# pathfiner.net
KiCad netlist of a schematic drawn in EAGLE
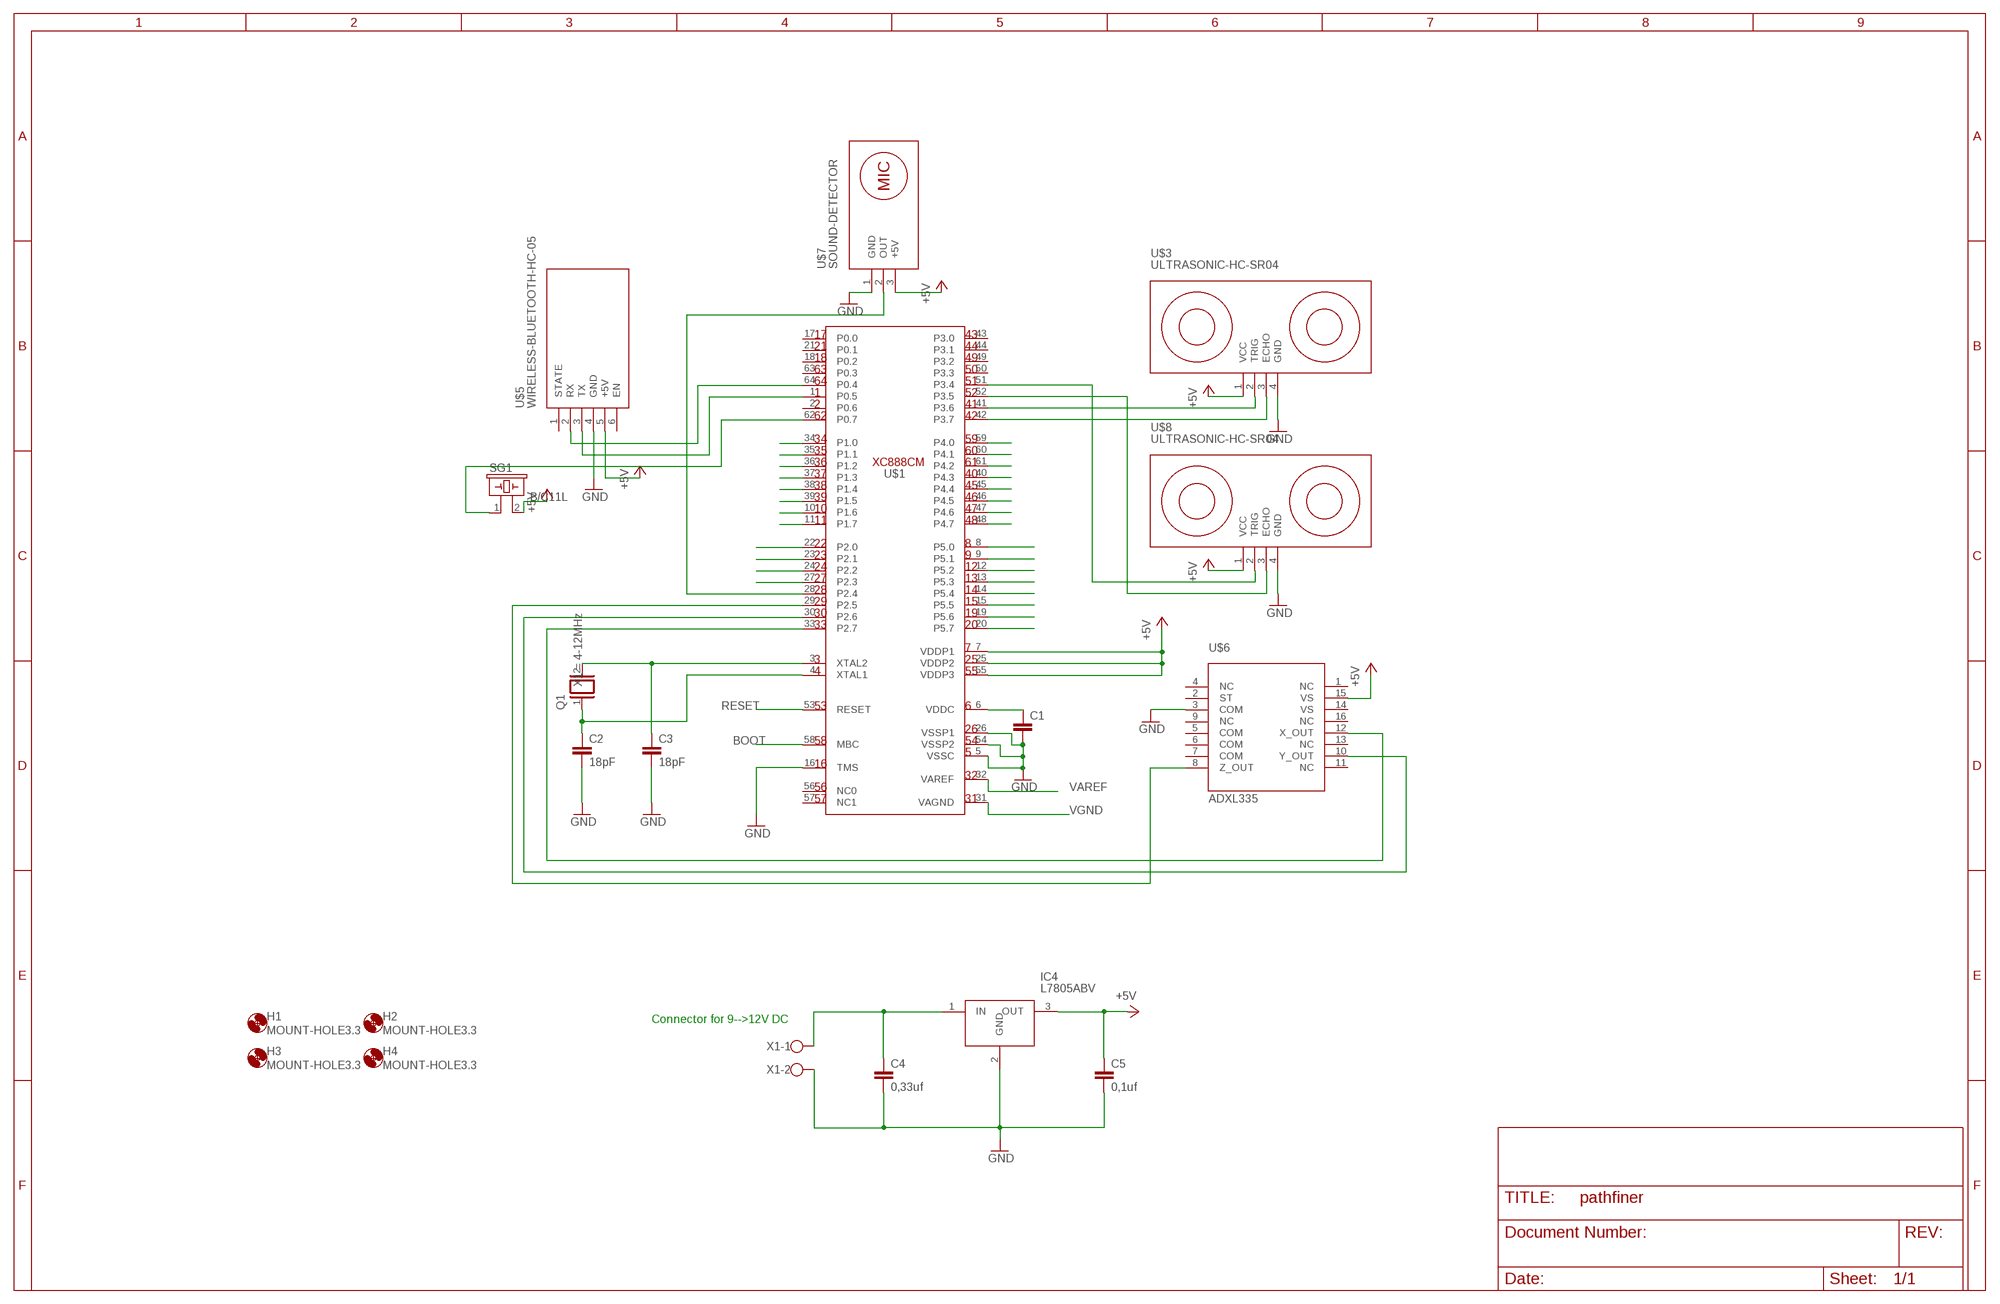
[diagram p0: schematic, sheet 1]

(export (version "E")
  (design (tool "Eeschema 10.0.6"))
  (components
    (comp (ref "C1")
      (value "C2,5-3")
      (footprint "eagle-import:C2.5-3")
      (libsource (lib "eagle-import") (part "C2,5-3"))
    )
    (comp (ref "C2")
      (value "18pF")
      (footprint "eagle-import:C2.5-3")
      (libsource (lib "eagle-import") (part "C2,5-3"))
    )
    (comp (ref "C3")
      (value "18pF")
      (footprint "eagle-import:C2.5-3")
      (libsource (lib "eagle-import") (part "C2,5-3"))
    )
    (comp (ref "C4")
      (value "0,33uf")
      (footprint "eagle-import:C025-030X050")
      (libsource (lib "eagle-import") (part "C-EU025-030X050"))
    )
    (comp (ref "C5")
      (value "0,1uf")
      (footprint "eagle-import:C025-030X050")
      (libsource (lib "eagle-import") (part "C-EU025-030X050"))
    )
    (comp (ref "H1")
      (value "MOUNT-HOLE3.3")
      (footprint "eagle-import:3,3")
      (libsource (lib "eagle-import") (part "MOUNT-HOLE3.3"))
    )
    (comp (ref "H2")
      (value "MOUNT-HOLE3.3")
      (footprint "eagle-import:3,3")
      (libsource (lib "eagle-import") (part "MOUNT-HOLE3.3"))
    )
    (comp (ref "H3")
      (value "MOUNT-HOLE3.3")
      (footprint "eagle-import:3,3")
      (libsource (lib "eagle-import") (part "MOUNT-HOLE3.3"))
    )
    (comp (ref "H4")
      (value "MOUNT-HOLE3.3")
      (footprint "eagle-import:3,3")
      (libsource (lib "eagle-import") (part "MOUNT-HOLE3.3"))
    )
    (comp (ref "IC4")
      (value "L7805ABV")
      (footprint "eagle-import:TO270P460X1020X2008-3P")
      (fields (field (name "MOUSER_PART_NUMBER") "511-L7805ABV") (field (name "RS_PART_NUMBER") "6869820P"))
      (libsource (lib "eagle-import") (part "L7805ABV"))
    )
    (comp (ref "Q1")
      (value "XTAL")
      (footprint "eagle-import:Q")
      (fields (field (name "X1") "4-12MHz"))
      (libsource (lib "eagle-import") (part "XTAL"))
    )
    (comp (ref "SG1")
      (value "B/C11L")
      (footprint "eagle-import:B_C11L")
      (libsource (lib "eagle-import") (part "B/C11L"))
    )
    (comp (ref "U$1")
      (value "XC888")
      (footprint "eagle-import:QFP50P1200X1200X160-64N")
      (libsource (lib "eagle-import") (part "XC888"))
    )
    (comp (ref "U$3")
      (value "ULTRASONIC-HC-SR04")
      (footprint "eagle-import:ULTRASONIC-HC-SR04")
      (libsource (lib "eagle-import") (part "ULTRASONIC-HC-SR04"))
    )
    (comp (ref "U$5")
      (value "WIRELESS-BLUETOOTH-HC-05")
      (footprint "eagle-import:WIRELESS-BLUETOOTH-HC-05")
      (libsource (lib "eagle-import") (part "WIRELESS-BLUETOOTH-HC-05"))
    )
    (comp (ref "U$6")
      (value "ADXL335")
      (footprint "eagle-import:LFCSP16")
      (libsource (lib "eagle-import") (part "ADXL335"))
    )
    (comp (ref "U$7")
      (value "SOUND-DETECTOR")
      (footprint "eagle-import:SOUND-DETECTOR")
      (libsource (lib "eagle-import") (part "SOUND-DETECTOR"))
    )
    (comp (ref "U$8")
      (value "ULTRASONIC-HC-SR04")
      (footprint "eagle-import:ULTRASONIC-HC-SR04")
      (libsource (lib "eagle-import") (part "ULTRASONIC-HC-SR04"))
    )
    (comp (ref "X1")
      (value "W237-102")
      (footprint "eagle-import:W237-102")
      (libsource (lib "eagle-import") (part "W237-102"))
    )
  )
  (nets
    (net (code "1") (name "+5V") (class "Default")
      (node (ref "C5") (pin "1") (pinfunction "1_1") (pintype "passive"))
      (node (ref "IC4") (pin "3") (pinfunction "OUT_3") (pintype "output"))
      (node (ref "SG1") (pin "2") (pinfunction "2_2") (pintype "passive"))
      (node (ref "U$1") (pin "25") (pinfunction "VDDP2_25") (pintype "bidirectional"))
      (node (ref "U$1") (pin "55") (pinfunction "VDDP3_55") (pintype "bidirectional"))
      (node (ref "U$1") (pin "7") (pinfunction "VDDP1_7") (pintype "bidirectional"))
      (node (ref "U$3") (pin "1") (pinfunction "VCC_1") (pintype "power_in"))
      (node (ref "U$5") (pin "5") (pinfunction "+5V_5") (pintype "power_in"))
      (node (ref "U$6") (pin "15") (pinfunction "VS_15") (pintype "bidirectional"))
      (node (ref "U$7") (pin "3") (pinfunction "+5V_3") (pintype "power_in"))
      (node (ref "U$8") (pin "1") (pinfunction "VCC_1") (pintype "power_in"))
    )
    (net (code "2") (name "/BOOT") (class "Default")
      (node (ref "U$1") (pin "58") (pinfunction "MBC_58") (pintype "bidirectional"))
    )
    (net (code "3") (name "/RESET") (class "Default")
      (node (ref "U$1") (pin "53") (pinfunction "RESET_53") (pintype "bidirectional"))
    )
    (net (code "4") (name "/VAREF") (class "Default")
      (node (ref "U$1") (pin "32") (pinfunction "VAREF_32") (pintype "bidirectional"))
    )
    (net (code "5") (name "/VGND") (class "Default")
      (node (ref "U$1") (pin "31") (pinfunction "VAGND_31") (pintype "bidirectional"))
    )
    (net (code "6") (name "GND") (class "Default")
      (node (ref "C1") (pin "2") (pinfunction "2_2") (pintype "passive"))
      (node (ref "C2") (pin "2") (pinfunction "2_2") (pintype "passive"))
      (node (ref "C3") (pin "2") (pinfunction "2_2") (pintype "passive"))
      (node (ref "C4") (pin "2") (pinfunction "2_2") (pintype "passive"))
      (node (ref "C5") (pin "2") (pinfunction "2_2") (pintype "passive"))
      (node (ref "IC4") (pin "2") (pinfunction "GND_2") (pintype "power_in"))
      (node (ref "U$1") (pin "16") (pinfunction "TMS_16") (pintype "bidirectional"))
      (node (ref "U$1") (pin "26") (pinfunction "VSSP1_26") (pintype "bidirectional"))
      (node (ref "U$1") (pin "5") (pinfunction "VSSC_5") (pintype "bidirectional"))
      (node (ref "U$1") (pin "54") (pinfunction "VSSP2_54") (pintype "bidirectional"))
      (node (ref "U$3") (pin "4") (pinfunction "GND_4") (pintype "power_in"))
      (node (ref "U$5") (pin "4") (pinfunction "GND_4") (pintype "power_in"))
      (node (ref "U$6") (pin "3") (pinfunction "COM_3") (pintype "bidirectional"))
      (node (ref "U$7") (pin "1") (pinfunction "GND_1") (pintype "power_in"))
      (node (ref "U$8") (pin "4") (pinfunction "GND_4") (pintype "power_in"))
      (node (ref "X1") (pin "2") (pinfunction "KL_2") (pintype "passive"))
    )
    (net (code "7") (name "Net-(IC4-IN)") (class "Default")
      (node (ref "C4") (pin "1") (pinfunction "1_1") (pintype "passive"))
      (node (ref "IC4") (pin "1") (pinfunction "IN_1") (pintype "input"))
      (node (ref "X1") (pin "1") (pinfunction "KL_1") (pintype "passive"))
    )
    (net (code "8") (name "Net-(U$1-P0.4)") (class "Default")
      (node (ref "U$1") (pin "64") (pinfunction "P0.4_64") (pintype "bidirectional"))
      (node (ref "U$5") (pin "2") (pinfunction "RX_2") (pintype "bidirectional"))
    )
    (net (code "9") (name "Net-(U$1-P0.5)") (class "Default")
      (node (ref "U$1") (pin "1") (pinfunction "P0.5_1") (pintype "bidirectional"))
      (node (ref "U$5") (pin "3") (pinfunction "TX_3") (pintype "bidirectional"))
    )
    (net (code "10") (name "Net-(U$1-P0.7)") (class "Default")
      (node (ref "SG1") (pin "1") (pinfunction "1_1") (pintype "passive"))
      (node (ref "U$1") (pin "62") (pinfunction "P0.7_62") (pintype "bidirectional"))
    )
    (net (code "11") (name "Net-(U$1-P2.4)") (class "Default")
      (node (ref "U$1") (pin "28") (pinfunction "P2.4_28") (pintype "bidirectional"))
      (node (ref "U$7") (pin "2") (pinfunction "OUT_2") (pintype "output"))
    )
    (net (code "12") (name "Net-(U$1-P2.5)") (class "Default")
      (node (ref "U$1") (pin "29") (pinfunction "P2.5_29") (pintype "bidirectional"))
      (node (ref "U$6") (pin "8") (pinfunction "Z_OUT_8") (pintype "bidirectional"))
    )
    (net (code "13") (name "Net-(U$1-P2.6)") (class "Default")
      (node (ref "U$1") (pin "30") (pinfunction "P2.6_30") (pintype "bidirectional"))
      (node (ref "U$6") (pin "10") (pinfunction "Y_OUT_10") (pintype "bidirectional"))
    )
    (net (code "14") (name "Net-(U$1-P2.7)") (class "Default")
      (node (ref "U$1") (pin "33") (pinfunction "P2.7_33") (pintype "bidirectional"))
      (node (ref "U$6") (pin "12") (pinfunction "X_OUT_12") (pintype "bidirectional"))
    )
    (net (code "15") (name "Net-(U$1-P3.4)") (class "Default")
      (node (ref "U$1") (pin "51") (pinfunction "P3.4_51") (pintype "bidirectional"))
      (node (ref "U$8") (pin "2") (pinfunction "TRIG_2") (pintype "input"))
    )
    (net (code "16") (name "Net-(U$1-P3.5)") (class "Default")
      (node (ref "U$1") (pin "52") (pinfunction "P3.5_52") (pintype "bidirectional"))
      (node (ref "U$8") (pin "3") (pinfunction "ECHO_3") (pintype "output"))
    )
    (net (code "17") (name "Net-(U$1-P3.6)") (class "Default")
      (node (ref "U$1") (pin "41") (pinfunction "P3.6_41") (pintype "bidirectional"))
      (node (ref "U$3") (pin "2") (pinfunction "TRIG_2") (pintype "input"))
    )
    (net (code "18") (name "Net-(U$1-P3.7)") (class "Default")
      (node (ref "U$1") (pin "42") (pinfunction "P3.7_42") (pintype "bidirectional"))
      (node (ref "U$3") (pin "3") (pinfunction "ECHO_3") (pintype "output"))
    )
    (net (code "19") (name "Net-(U$1-VDDC)") (class "Default")
      (node (ref "C1") (pin "1") (pinfunction "1_1") (pintype "passive"))
      (node (ref "U$1") (pin "6") (pinfunction "VDDC_6") (pintype "bidirectional"))
    )
    (net (code "20") (name "Net-(U$1-XTAL1)") (class "Default")
      (node (ref "C2") (pin "1") (pinfunction "1_1") (pintype "passive"))
      (node (ref "Q1") (pin "1") (pinfunction "1_1") (pintype "passive"))
      (node (ref "U$1") (pin "4") (pinfunction "XTAL1_4") (pintype "bidirectional"))
    )
    (net (code "21") (name "Net-(U$1-XTAL2)") (class "Default")
      (node (ref "C3") (pin "1") (pinfunction "1_1") (pintype "passive"))
      (node (ref "Q1") (pin "2") (pinfunction "2_2") (pintype "passive"))
      (node (ref "U$1") (pin "3") (pinfunction "XTAL2_3") (pintype "bidirectional"))
    )
    (net (code "22") (name "unconnected-(U$1-NC0-Pad56)") (class "Default")
      (node (ref "U$1") (pin "56") (pinfunction "NC0_56") (pintype "bidirectional"))
    )
    (net (code "23") (name "unconnected-(U$1-NC1-Pad57)") (class "Default")
      (node (ref "U$1") (pin "57") (pinfunction "NC1_57") (pintype "bidirectional"))
    )
    (net (code "24") (name "unconnected-(U$1-P0.0-Pad17)") (class "Default")
      (node (ref "U$1") (pin "17") (pinfunction "P0.0_17") (pintype "bidirectional"))
    )
    (net (code "25") (name "unconnected-(U$1-P0.1-Pad21)") (class "Default")
      (node (ref "U$1") (pin "21") (pinfunction "P0.1_21") (pintype "bidirectional"))
    )
    (net (code "26") (name "unconnected-(U$1-P0.2-Pad18)") (class "Default")
      (node (ref "U$1") (pin "18") (pinfunction "P0.2_18") (pintype "bidirectional"))
    )
    (net (code "27") (name "unconnected-(U$1-P0.3-Pad63)") (class "Default")
      (node (ref "U$1") (pin "63") (pinfunction "P0.3_63") (pintype "bidirectional"))
    )
    (net (code "28") (name "unconnected-(U$1-P0.6-Pad2)") (class "Default")
      (node (ref "U$1") (pin "2") (pinfunction "P0.6_2") (pintype "bidirectional"))
    )
    (net (code "29") (name "unconnected-(U$1-P1.0-Pad34)") (class "Default")
      (node (ref "U$1") (pin "34") (pinfunction "P1.0_34") (pintype "bidirectional"))
    )
    (net (code "30") (name "unconnected-(U$1-P1.1-Pad35)") (class "Default")
      (node (ref "U$1") (pin "35") (pinfunction "P1.1_35") (pintype "bidirectional"))
    )
    (net (code "31") (name "unconnected-(U$1-P1.2-Pad36)") (class "Default")
      (node (ref "U$1") (pin "36") (pinfunction "P1.2_36") (pintype "bidirectional"))
    )
    (net (code "32") (name "unconnected-(U$1-P1.3-Pad37)") (class "Default")
      (node (ref "U$1") (pin "37") (pinfunction "P1.3_37") (pintype "bidirectional"))
    )
    (net (code "33") (name "unconnected-(U$1-P1.4-Pad38)") (class "Default")
      (node (ref "U$1") (pin "38") (pinfunction "P1.4_38") (pintype "bidirectional"))
    )
    (net (code "34") (name "unconnected-(U$1-P1.5-Pad39)") (class "Default")
      (node (ref "U$1") (pin "39") (pinfunction "P1.5_39") (pintype "bidirectional"))
    )
    (net (code "35") (name "unconnected-(U$1-P1.6-Pad10)") (class "Default")
      (node (ref "U$1") (pin "10") (pinfunction "P1.6_10") (pintype "bidirectional"))
    )
    (net (code "36") (name "unconnected-(U$1-P1.7-Pad11)") (class "Default")
      (node (ref "U$1") (pin "11") (pinfunction "P1.7_11") (pintype "bidirectional"))
    )
    (net (code "37") (name "unconnected-(U$1-P2.0-Pad22)") (class "Default")
      (node (ref "U$1") (pin "22") (pinfunction "P2.0_22") (pintype "bidirectional"))
    )
    (net (code "38") (name "unconnected-(U$1-P2.1-Pad23)") (class "Default")
      (node (ref "U$1") (pin "23") (pinfunction "P2.1_23") (pintype "bidirectional"))
    )
    (net (code "39") (name "unconnected-(U$1-P2.2-Pad24)") (class "Default")
      (node (ref "U$1") (pin "24") (pinfunction "P2.2_24") (pintype "bidirectional"))
    )
    (net (code "40") (name "unconnected-(U$1-P2.3-Pad27)") (class "Default")
      (node (ref "U$1") (pin "27") (pinfunction "P2.3_27") (pintype "bidirectional"))
    )
    (net (code "41") (name "unconnected-(U$1-P3.0-Pad43)") (class "Default")
      (node (ref "U$1") (pin "43") (pinfunction "P3.0_43") (pintype "bidirectional"))
    )
    (net (code "42") (name "unconnected-(U$1-P3.1-Pad44)") (class "Default")
      (node (ref "U$1") (pin "44") (pinfunction "P3.1_44") (pintype "bidirectional"))
    )
    (net (code "43") (name "unconnected-(U$1-P3.2-Pad49)") (class "Default")
      (node (ref "U$1") (pin "49") (pinfunction "P3.2_49") (pintype "bidirectional"))
    )
    (net (code "44") (name "unconnected-(U$1-P3.3-Pad50)") (class "Default")
      (node (ref "U$1") (pin "50") (pinfunction "P3.3_50") (pintype "bidirectional"))
    )
    (net (code "45") (name "unconnected-(U$1-P4.0-Pad59)") (class "Default")
      (node (ref "U$1") (pin "59") (pinfunction "P4.0_59") (pintype "bidirectional"))
    )
    (net (code "46") (name "unconnected-(U$1-P4.1-Pad60)") (class "Default")
      (node (ref "U$1") (pin "60") (pinfunction "P4.1_60") (pintype "bidirectional"))
    )
    (net (code "47") (name "unconnected-(U$1-P4.2-Pad61)") (class "Default")
      (node (ref "U$1") (pin "61") (pinfunction "P4.2_61") (pintype "bidirectional"))
    )
    (net (code "48") (name "unconnected-(U$1-P4.3-Pad40)") (class "Default")
      (node (ref "U$1") (pin "40") (pinfunction "P4.3_40") (pintype "bidirectional"))
    )
    (net (code "49") (name "unconnected-(U$1-P4.4-Pad45)") (class "Default")
      (node (ref "U$1") (pin "45") (pinfunction "P4.4_45") (pintype "bidirectional"))
    )
    (net (code "50") (name "unconnected-(U$1-P4.5-Pad46)") (class "Default")
      (node (ref "U$1") (pin "46") (pinfunction "P4.5_46") (pintype "bidirectional"))
    )
    (net (code "51") (name "unconnected-(U$1-P4.6-Pad47)") (class "Default")
      (node (ref "U$1") (pin "47") (pinfunction "P4.6_47") (pintype "bidirectional"))
    )
    (net (code "52") (name "unconnected-(U$1-P4.7-Pad48)") (class "Default")
      (node (ref "U$1") (pin "48") (pinfunction "P4.7_48") (pintype "bidirectional"))
    )
    (net (code "53") (name "unconnected-(U$1-P5.0-Pad8)") (class "Default")
      (node (ref "U$1") (pin "8") (pinfunction "P5.0_8") (pintype "bidirectional"))
    )
    (net (code "54") (name "unconnected-(U$1-P5.1-Pad9)") (class "Default")
      (node (ref "U$1") (pin "9") (pinfunction "P5.1_9") (pintype "bidirectional"))
    )
    (net (code "55") (name "unconnected-(U$1-P5.2-Pad12)") (class "Default")
      (node (ref "U$1") (pin "12") (pinfunction "P5.2_12") (pintype "bidirectional"))
    )
    (net (code "56") (name "unconnected-(U$1-P5.3-Pad13)") (class "Default")
      (node (ref "U$1") (pin "13") (pinfunction "P5.3_13") (pintype "bidirectional"))
    )
    (net (code "57") (name "unconnected-(U$1-P5.4-Pad14)") (class "Default")
      (node (ref "U$1") (pin "14") (pinfunction "P5.4_14") (pintype "bidirectional"))
    )
    (net (code "58") (name "unconnected-(U$1-P5.5-Pad15)") (class "Default")
      (node (ref "U$1") (pin "15") (pinfunction "P5.5_15") (pintype "bidirectional"))
    )
    (net (code "59") (name "unconnected-(U$1-P5.6-Pad19)") (class "Default")
      (node (ref "U$1") (pin "19") (pinfunction "P5.6_19") (pintype "bidirectional"))
    )
    (net (code "60") (name "unconnected-(U$1-P5.7-Pad20)") (class "Default")
      (node (ref "U$1") (pin "20") (pinfunction "P5.7_20") (pintype "bidirectional"))
    )
    (net (code "61") (name "unconnected-(U$5-EN-Pad6)") (class "Default")
      (node (ref "U$5") (pin "6") (pinfunction "EN_6") (pintype "bidirectional"))
    )
    (net (code "62") (name "unconnected-(U$5-STATE-Pad1)") (class "Default")
      (node (ref "U$5") (pin "1") (pinfunction "STATE_1") (pintype "bidirectional"))
    )
    (net (code "63") (name "unconnected-(U$6-COM-Pad5)") (class "Default")
      (node (ref "U$6") (pin "5") (pinfunction "COM_5") (pintype "bidirectional"))
    )
    (net (code "64") (name "unconnected-(U$6-COM-Pad6)") (class "Default")
      (node (ref "U$6") (pin "6") (pinfunction "COM_6") (pintype "bidirectional"))
    )
    (net (code "65") (name "unconnected-(U$6-COM-Pad7)") (class "Default")
      (node (ref "U$6") (pin "7") (pinfunction "COM_7") (pintype "bidirectional"))
    )
    (net (code "66") (name "unconnected-(U$6-NC-Pad1)") (class "Default")
      (node (ref "U$6") (pin "1") (pinfunction "NC_1") (pintype "bidirectional"))
    )
    (net (code "67") (name "unconnected-(U$6-NC-Pad4)") (class "Default")
      (node (ref "U$6") (pin "4") (pinfunction "NC_4") (pintype "bidirectional"))
    )
    (net (code "68") (name "unconnected-(U$6-NC-Pad9)") (class "Default")
      (node (ref "U$6") (pin "9") (pinfunction "NC_9") (pintype "bidirectional"))
    )
    (net (code "69") (name "unconnected-(U$6-NC-Pad11)") (class "Default")
      (node (ref "U$6") (pin "11") (pinfunction "NC_11") (pintype "bidirectional"))
    )
    (net (code "70") (name "unconnected-(U$6-NC-Pad13)") (class "Default")
      (node (ref "U$6") (pin "13") (pinfunction "NC_13") (pintype "bidirectional"))
    )
    (net (code "71") (name "unconnected-(U$6-NC-Pad16)") (class "Default")
      (node (ref "U$6") (pin "16") (pinfunction "NC_16") (pintype "bidirectional"))
    )
    (net (code "72") (name "unconnected-(U$6-ST-Pad2)") (class "Default")
      (node (ref "U$6") (pin "2") (pinfunction "ST_2") (pintype "bidirectional"))
    )
    (net (code "73") (name "unconnected-(U$6-VS-Pad14)") (class "Default")
      (node (ref "U$6") (pin "14") (pinfunction "VS_14") (pintype "bidirectional"))
    )
  )
)
